# base.net
KiCad netlist of a schematic drawn in EAGLE
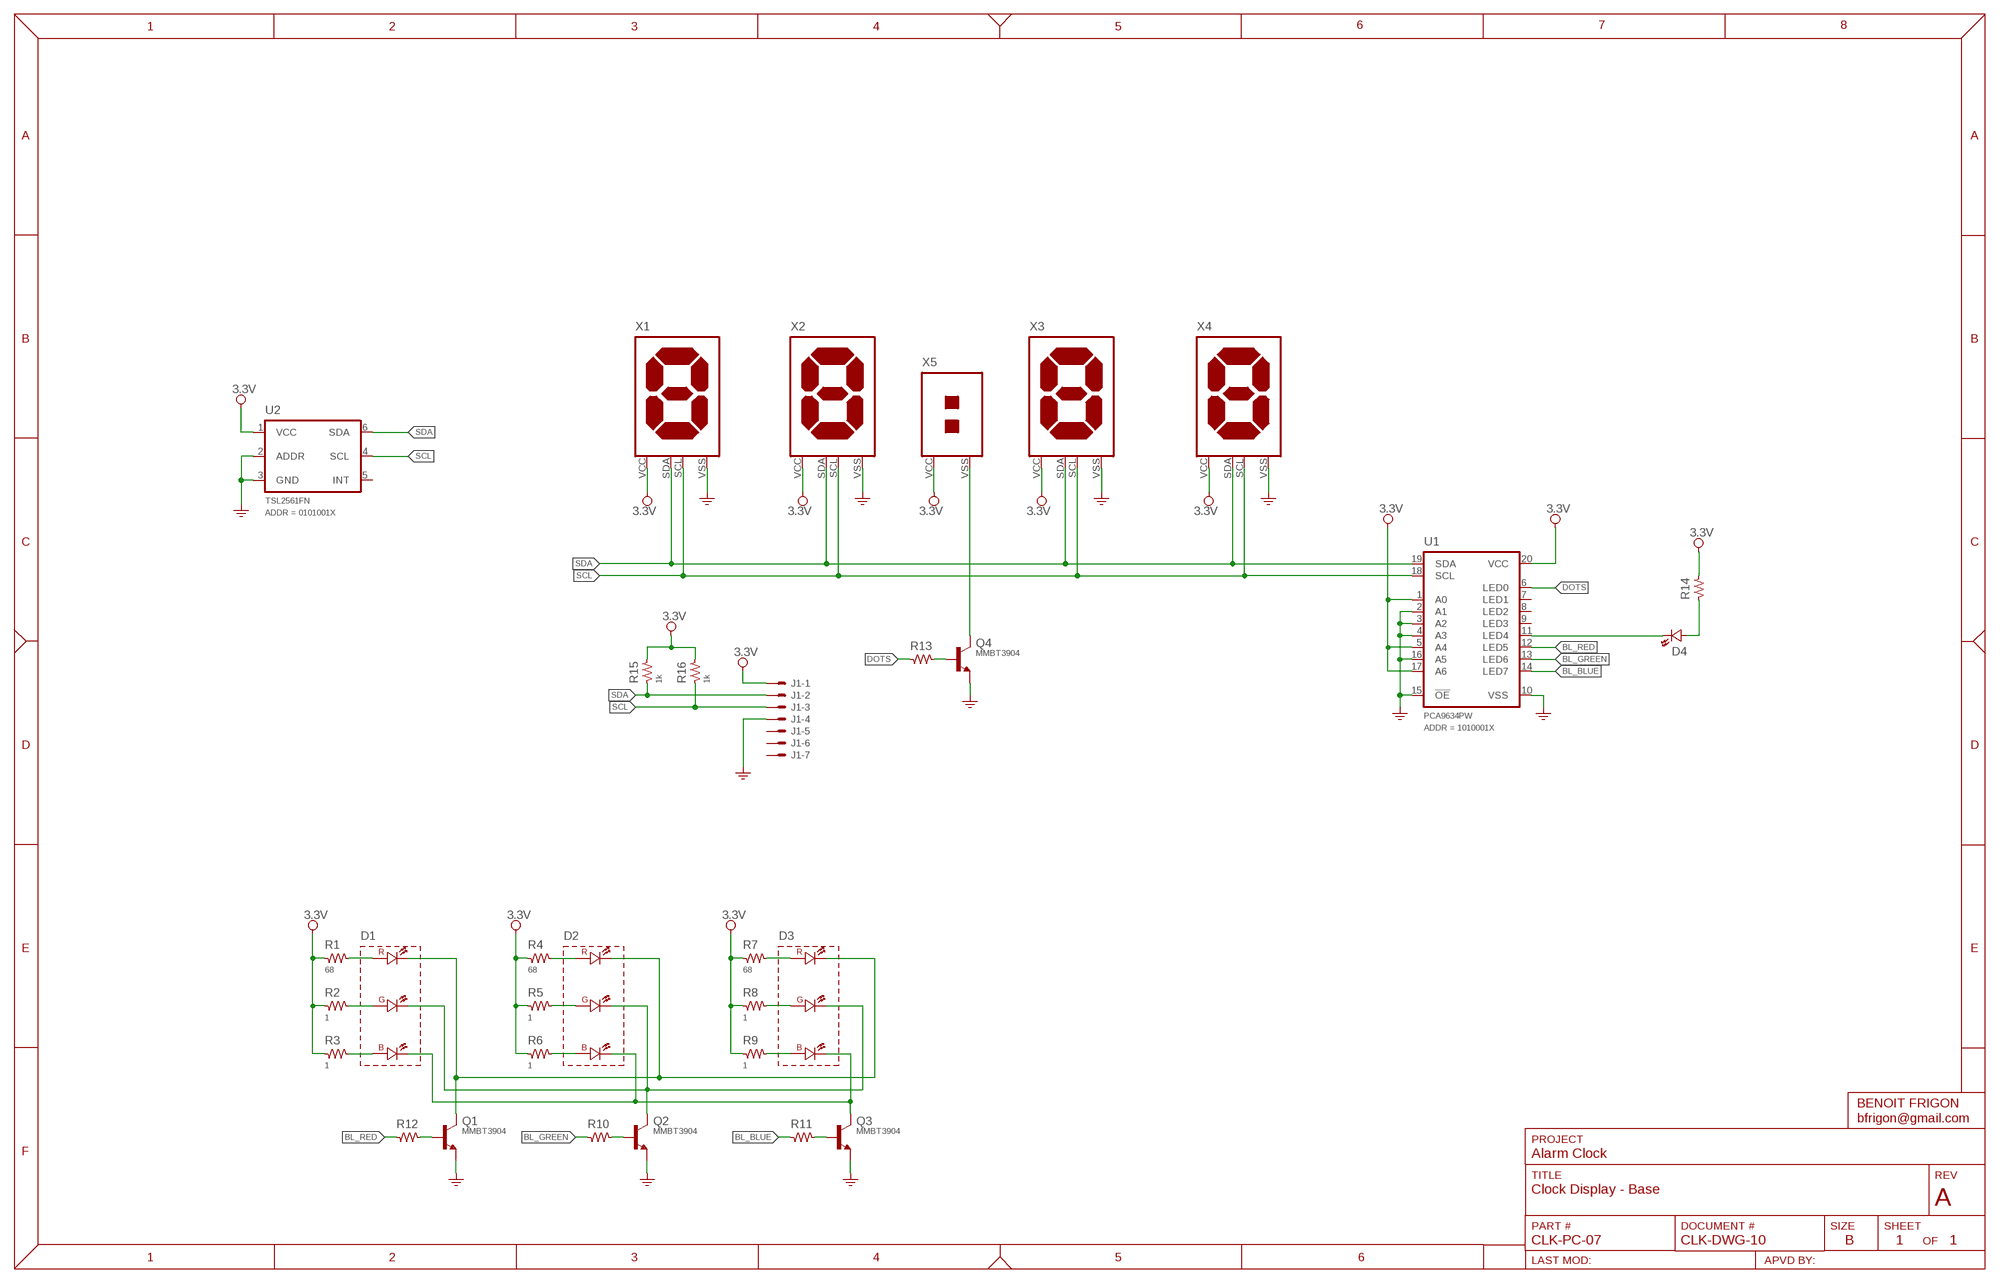
[diagram p0: schematic, sheet 1]

(export (version "E")
  (design (tool "Eeschema 10.0.6"))
  (components
    (comp (ref "D1")
      (value "SMP6-RGB")
      (footprint "eagle-import:LED_RGB_PLCC6")
      (fields (field (name "MFG") "Bivar") (field (name "MFG_1") "BIVAR") (field (name "SKU") "SMP6-RGB"))
      (libsource (lib "eagle-import") (part "SMP6-RGB"))
    )
    (comp (ref "D2")
      (value "SMP6-RGB")
      (footprint "eagle-import:LED_RGB_PLCC6")
      (fields (field (name "MFG") "Bivar"))
      (libsource (lib "eagle-import") (part "SMP6-RGB"))
    )
    (comp (ref "D3")
      (value "SMP6-RGB")
      (footprint "eagle-import:LED_RGB_PLCC6")
      (fields (field (name "MFG") "Bivar"))
      (libsource (lib "eagle-import") (part "SMP6-RGB"))
    )
    (comp (ref "D4")
      (value "{ATTR:COLOR}")
      (footprint "eagle-import:LED_3MM")
      (libsource (lib "eagle-import") (part "LED-T1"))
    )
    (comp (ref "J1")
      (value "SNG-2MM-HEADER-07-V")
      (footprint "eagle-import:DF3X-7P-2DSA")
      (fields
        (field (name "MFG") "Hirose Electronic")
        (field (name "PART_NO") "DF3A-7P-2DSA")
        (field (name "PRICE") "0.37")
        (field (name "SKU") "H2099-ND")
        (field (name "SUPPLIER") "Digi-Key")
      )
      (libsource (lib "eagle-import") (part "SNG-2MM-HEADER-07-V"))
    )
    (comp (ref "Q1")
      (value "MMBT3904")
      (footprint "eagle-import:SOT23")
      (libsource (lib "eagle-import") (part "MMBT3904"))
    )
    (comp (ref "Q2")
      (value "MMBT3904")
      (footprint "eagle-import:SOT23")
      (libsource (lib "eagle-import") (part "MMBT3904"))
    )
    (comp (ref "Q3")
      (value "MMBT3904")
      (footprint "eagle-import:SOT23")
      (libsource (lib "eagle-import") (part "MMBT3904"))
    )
    (comp (ref "Q4")
      (value "MMBT3904")
      (footprint "eagle-import:SOT23")
      (libsource (lib "eagle-import") (part "MMBT3904"))
    )
    (comp (ref "R1")
      (value "68")
      (footprint "eagle-import:SMD_0603")
      (libsource (lib "eagle-import") (part "RES-0603"))
    )
    (comp (ref "R2")
      (value "1")
      (footprint "eagle-import:SMD_0603")
      (description "{DESCRIPTION} - SMT 0603 - {VALUE}")
      (fields (field (name "PACKAGE") "SMT 0603"))
      (libsource (lib "eagle-import") (part "RES-0603"))
    )
    (comp (ref "R3")
      (value "1")
      (footprint "eagle-import:SMD_0603")
      (description "{DESCRIPTION} - SMT 0603 - {VALUE}")
      (fields (field (name "PACKAGE") "SMT 0603"))
      (libsource (lib "eagle-import") (part "RES-0603"))
    )
    (comp (ref "R4")
      (value "68")
      (footprint "eagle-import:SMD_0603")
      (libsource (lib "eagle-import") (part "RES-0603"))
    )
    (comp (ref "R5")
      (value "1")
      (footprint "eagle-import:SMD_0603")
      (description "{DESCRIPTION} - SMT 0603 - {VALUE}")
      (fields (field (name "PACKAGE") "SMT 0603"))
      (libsource (lib "eagle-import") (part "RES-0603"))
    )
    (comp (ref "R6")
      (value "1")
      (footprint "eagle-import:SMD_0603")
      (description "{DESCRIPTION} - SMT 0603 - {VALUE}")
      (fields (field (name "PACKAGE") "SMT 0603"))
      (libsource (lib "eagle-import") (part "RES-0603"))
    )
    (comp (ref "R7")
      (value "68")
      (footprint "eagle-import:SMD_0603")
      (libsource (lib "eagle-import") (part "RES-0603"))
    )
    (comp (ref "R8")
      (value "1")
      (footprint "eagle-import:SMD_0603")
      (description "{DESCRIPTION} - SMT 0603 - {VALUE}")
      (fields (field (name "PACKAGE") "SMT 0603"))
      (libsource (lib "eagle-import") (part "RES-0603"))
    )
    (comp (ref "R9")
      (value "1")
      (footprint "eagle-import:SMD_0603")
      (description "{DESCRIPTION} - SMT 0603 - {VALUE}")
      (fields (field (name "PACKAGE") "SMT 0603"))
      (libsource (lib "eagle-import") (part "RES-0603"))
    )
    (comp (ref "R10")
      (value "RES-0603")
      (footprint "eagle-import:SMD_0603")
      (libsource (lib "eagle-import") (part "RES-0603"))
    )
    (comp (ref "R11")
      (value "RES-0603")
      (footprint "eagle-import:SMD_0603")
      (libsource (lib "eagle-import") (part "RES-0603"))
    )
    (comp (ref "R12")
      (value "RES-0603")
      (footprint "eagle-import:SMD_0603")
      (libsource (lib "eagle-import") (part "RES-0603"))
    )
    (comp (ref "R13")
      (value "RES-0603")
      (footprint "eagle-import:SMD_0603")
      (description "{DESCRIPTION} - SMT 0603 - {VALUE}")
      (fields (field (name "PACKAGE") "SMT 0603"))
      (libsource (lib "eagle-import") (part "RES-0603"))
    )
    (comp (ref "R14")
      (value "RES-0603")
      (footprint "eagle-import:SMD_0603")
      (libsource (lib "eagle-import") (part "RES-0603"))
    )
    (comp (ref "R15")
      (value "1k")
      (footprint "eagle-import:SMD_0603")
      (libsource (lib "eagle-import") (part "RES-0603"))
    )
    (comp (ref "R16")
      (value "1k")
      (footprint "eagle-import:SMD_0603")
      (libsource (lib "eagle-import") (part "RES-0603"))
    )
    (comp (ref "U1")
      (value "PCA9634PW")
      (footprint "eagle-import:TSSOP20")
      (fields (field (name "MFG") "NXP Semiconductors") (field (name "ADDR") "1010001X"))
      (libsource (lib "eagle-import") (part "PCA9634PW"))
    )
    (comp (ref "U2")
      (value "TSL2561FN")
      (footprint "eagle-import:DFN-6")
      (fields (field (name "ADDR") "0101001X"))
      (libsource (lib "eagle-import") (part "TSL2561FN"))
    )
    (comp (ref "X1")
      (value "CLOCK_LED_SEGMENT")
      (footprint "eagle-import:CLOCK_LED_SEGMENT")
      (libsource (lib "eagle-import") (part "CLOCK_LED_SEGMENT"))
    )
    (comp (ref "X2")
      (value "CLOCK_LED_SEGMENT")
      (footprint "eagle-import:CLOCK_LED_SEGMENT")
      (libsource (lib "eagle-import") (part "CLOCK_LED_SEGMENT"))
    )
    (comp (ref "X3")
      (value "CLOCK_LED_SEGMENT")
      (footprint "eagle-import:CLOCK_LED_SEGMENT")
      (libsource (lib "eagle-import") (part "CLOCK_LED_SEGMENT"))
    )
    (comp (ref "X4")
      (value "CLOCK_LED_SEGMENT")
      (footprint "eagle-import:CLOCK_LED_SEGMENT")
      (libsource (lib "eagle-import") (part "CLOCK_LED_SEGMENT"))
    )
    (comp (ref "X5")
      (value "CLOCK_LED_DOTS")
      (footprint "eagle-import:CLOCK_LED_DOTS")
      (libsource (lib "eagle-import") (part "CLOCK_LED_DOTS"))
    )
  )
  (nets
    (net (code "1") (name "3.3V") (class "Default")
      (node (ref "J1") (pin "1") (pinfunction "S_1") (pintype "bidirectional"))
      (node (ref "R1") (pin "1") (pinfunction "1_1") (pintype "passive"))
      (node (ref "R14") (pin "2") (pinfunction "2_2") (pintype "passive"))
      (node (ref "R15") (pin "2") (pinfunction "2_2") (pintype "passive"))
      (node (ref "R16") (pin "2") (pinfunction "2_2") (pintype "passive"))
      (node (ref "R2") (pin "1") (pinfunction "1_1") (pintype "passive"))
      (node (ref "R3") (pin "1") (pinfunction "1_1") (pintype "passive"))
      (node (ref "R4") (pin "1") (pinfunction "1_1") (pintype "passive"))
      (node (ref "R5") (pin "1") (pinfunction "1_1") (pintype "passive"))
      (node (ref "R6") (pin "1") (pinfunction "1_1") (pintype "passive"))
      (node (ref "R7") (pin "1") (pinfunction "1_1") (pintype "passive"))
      (node (ref "R8") (pin "1") (pinfunction "1_1") (pintype "passive"))
      (node (ref "R9") (pin "1") (pinfunction "1_1") (pintype "passive"))
      (node (ref "U1") (pin "1") (pinfunction "A0_1") (pintype "bidirectional"))
      (node (ref "U1") (pin "17") (pinfunction "A6_17") (pintype "bidirectional"))
      (node (ref "U1") (pin "20") (pinfunction "VCC_20") (pintype "bidirectional"))
      (node (ref "U1") (pin "5") (pinfunction "A4_5") (pintype "bidirectional"))
      (node (ref "U2") (pin "1") (pinfunction "VCC_1") (pintype "bidirectional"))
      (node (ref "X1") (pin "VCC") (pinfunction "VCC_VCC") (pintype "bidirectional"))
      (node (ref "X2") (pin "VCC") (pinfunction "VCC_VCC") (pintype "bidirectional"))
      (node (ref "X3") (pin "VCC") (pinfunction "VCC_VCC") (pintype "bidirectional"))
      (node (ref "X4") (pin "VCC") (pinfunction "VCC_VCC") (pintype "bidirectional"))
      (node (ref "X5") (pin "VCC") (pinfunction "VCC_VCC") (pintype "bidirectional"))
    )
    (net (code "2") (name "BL_BLUE") (class "Default")
      (node (ref "R11") (pin "1") (pinfunction "1_1") (pintype "passive"))
      (node (ref "U1") (pin "14") (pinfunction "LED7_14") (pintype "bidirectional"))
    )
    (net (code "3") (name "BL_GREEN") (class "Default")
      (node (ref "R10") (pin "1") (pinfunction "1_1") (pintype "passive"))
      (node (ref "U1") (pin "13") (pinfunction "LED6_13") (pintype "bidirectional"))
    )
    (net (code "4") (name "BL_RED") (class "Default")
      (node (ref "R12") (pin "1") (pinfunction "1_1") (pintype "passive"))
      (node (ref "U1") (pin "12") (pinfunction "LED5_12") (pintype "bidirectional"))
    )
    (net (code "5") (name "DOTS") (class "Default")
      (node (ref "R13") (pin "1") (pinfunction "1_1") (pintype "passive"))
      (node (ref "U1") (pin "6") (pinfunction "LED0_6") (pintype "bidirectional"))
    )
    (net (code "6") (name "GND") (class "Default")
      (node (ref "J1") (pin "4") (pinfunction "S_4") (pintype "bidirectional"))
      (node (ref "Q1") (pin "2") (pinfunction "E_2") (pintype "passive"))
      (node (ref "Q2") (pin "2") (pinfunction "E_2") (pintype "passive"))
      (node (ref "Q3") (pin "2") (pinfunction "E_2") (pintype "passive"))
      (node (ref "Q4") (pin "2") (pinfunction "E_2") (pintype "passive"))
      (node (ref "U1") (pin "10") (pinfunction "VSS_10") (pintype "bidirectional"))
      (node (ref "U1") (pin "15") (pinfunction "~{OE}_15") (pintype "bidirectional"))
      (node (ref "U1") (pin "16") (pinfunction "A5_16") (pintype "bidirectional"))
      (node (ref "U1") (pin "2") (pinfunction "A1_2") (pintype "bidirectional"))
      (node (ref "U1") (pin "3") (pinfunction "A2_3") (pintype "bidirectional"))
      (node (ref "U1") (pin "4") (pinfunction "A3_4") (pintype "bidirectional"))
      (node (ref "U2") (pin "2") (pinfunction "ADDR_2") (pintype "bidirectional"))
      (node (ref "U2") (pin "3") (pinfunction "GND_3") (pintype "bidirectional"))
      (node (ref "X1") (pin "VSS") (pinfunction "VSS_VSS") (pintype "bidirectional"))
      (node (ref "X2") (pin "VSS") (pinfunction "VSS_VSS") (pintype "bidirectional"))
      (node (ref "X3") (pin "VSS") (pinfunction "VSS_VSS") (pintype "bidirectional"))
      (node (ref "X4") (pin "VSS") (pinfunction "VSS_VSS") (pintype "bidirectional"))
    )
    (net (code "7") (name "Net-(D1-BA)") (class "Default")
      (node (ref "D1") (pin "6") (pinfunction "BA_6") (pintype "passive"))
      (node (ref "R3") (pin "2") (pinfunction "2_2") (pintype "passive"))
    )
    (net (code "8") (name "Net-(D1-BK)") (class "Default")
      (node (ref "D1") (pin "5") (pinfunction "BK_5") (pintype "passive"))
      (node (ref "D2") (pin "5") (pinfunction "BK_5") (pintype "passive"))
      (node (ref "D3") (pin "5") (pinfunction "BK_5") (pintype "passive"))
      (node (ref "Q3") (pin "3") (pinfunction "C_3") (pintype "passive"))
    )
    (net (code "9") (name "Net-(D1-GA)") (class "Default")
      (node (ref "D1") (pin "2") (pinfunction "GA_2") (pintype "passive"))
      (node (ref "R2") (pin "2") (pinfunction "2_2") (pintype "passive"))
    )
    (net (code "10") (name "Net-(D1-GK)") (class "Default")
      (node (ref "D1") (pin "1") (pinfunction "GK_1") (pintype "passive"))
      (node (ref "D2") (pin "1") (pinfunction "GK_1") (pintype "passive"))
      (node (ref "D3") (pin "1") (pinfunction "GK_1") (pintype "passive"))
      (node (ref "Q2") (pin "3") (pinfunction "C_3") (pintype "passive"))
    )
    (net (code "11") (name "Net-(D1-RA)") (class "Default")
      (node (ref "D1") (pin "4") (pinfunction "RA_4") (pintype "passive"))
      (node (ref "R1") (pin "2") (pinfunction "2_2") (pintype "passive"))
    )
    (net (code "12") (name "Net-(D1-RK)") (class "Default")
      (node (ref "D1") (pin "3") (pinfunction "RK_3") (pintype "passive"))
      (node (ref "D2") (pin "3") (pinfunction "RK_3") (pintype "passive"))
      (node (ref "D3") (pin "3") (pinfunction "RK_3") (pintype "passive"))
      (node (ref "Q1") (pin "3") (pinfunction "C_3") (pintype "passive"))
    )
    (net (code "13") (name "Net-(D2-BA)") (class "Default")
      (node (ref "D2") (pin "6") (pinfunction "BA_6") (pintype "passive"))
      (node (ref "R6") (pin "2") (pinfunction "2_2") (pintype "passive"))
    )
    (net (code "14") (name "Net-(D2-GA)") (class "Default")
      (node (ref "D2") (pin "2") (pinfunction "GA_2") (pintype "passive"))
      (node (ref "R5") (pin "2") (pinfunction "2_2") (pintype "passive"))
    )
    (net (code "15") (name "Net-(D2-RA)") (class "Default")
      (node (ref "D2") (pin "4") (pinfunction "RA_4") (pintype "passive"))
      (node (ref "R4") (pin "2") (pinfunction "2_2") (pintype "passive"))
    )
    (net (code "16") (name "Net-(D3-BA)") (class "Default")
      (node (ref "D3") (pin "6") (pinfunction "BA_6") (pintype "passive"))
      (node (ref "R9") (pin "2") (pinfunction "2_2") (pintype "passive"))
    )
    (net (code "17") (name "Net-(D3-GA)") (class "Default")
      (node (ref "D3") (pin "2") (pinfunction "GA_2") (pintype "passive"))
      (node (ref "R8") (pin "2") (pinfunction "2_2") (pintype "passive"))
    )
    (net (code "18") (name "Net-(D3-RA)") (class "Default")
      (node (ref "D3") (pin "4") (pinfunction "RA_4") (pintype "passive"))
      (node (ref "R7") (pin "2") (pinfunction "2_2") (pintype "passive"))
    )
    (net (code "19") (name "Net-(D4-PadA)") (class "Default")
      (node (ref "D4") (pin "A") (pinfunction "A_A") (pintype "passive"))
      (node (ref "R14") (pin "1") (pinfunction "1_1") (pintype "passive"))
    )
    (net (code "20") (name "Net-(Q1-B)") (class "Default")
      (node (ref "Q1") (pin "1") (pinfunction "B_1") (pintype "passive"))
      (node (ref "R12") (pin "2") (pinfunction "2_2") (pintype "passive"))
    )
    (net (code "21") (name "Net-(Q2-B)") (class "Default")
      (node (ref "Q2") (pin "1") (pinfunction "B_1") (pintype "passive"))
      (node (ref "R10") (pin "2") (pinfunction "2_2") (pintype "passive"))
    )
    (net (code "22") (name "Net-(Q3-B)") (class "Default")
      (node (ref "Q3") (pin "1") (pinfunction "B_1") (pintype "passive"))
      (node (ref "R11") (pin "2") (pinfunction "2_2") (pintype "passive"))
    )
    (net (code "23") (name "Net-(Q4-B)") (class "Default")
      (node (ref "Q4") (pin "1") (pinfunction "B_1") (pintype "passive"))
      (node (ref "R13") (pin "2") (pinfunction "2_2") (pintype "passive"))
    )
    (net (code "24") (name "Net-(Q4-C)") (class "Default")
      (node (ref "Q4") (pin "3") (pinfunction "C_3") (pintype "passive"))
      (node (ref "X5") (pin "VSS") (pinfunction "VSS_VSS") (pintype "bidirectional"))
    )
    (net (code "25") (name "Net-(U1-LED4)") (class "Default")
      (node (ref "D4") (pin "K") (pinfunction "K_K") (pintype "passive"))
      (node (ref "U1") (pin "11") (pinfunction "LED4_11") (pintype "bidirectional"))
    )
    (net (code "26") (name "SCL") (class "Default")
      (node (ref "J1") (pin "3") (pinfunction "S_3") (pintype "bidirectional"))
      (node (ref "R16") (pin "1") (pinfunction "1_1") (pintype "passive"))
      (node (ref "U1") (pin "18") (pinfunction "SCL_18") (pintype "bidirectional"))
      (node (ref "U2") (pin "4") (pinfunction "SCL_4") (pintype "bidirectional"))
      (node (ref "X1") (pin "SCL") (pinfunction "SCL_SCL") (pintype "bidirectional"))
      (node (ref "X2") (pin "SCL") (pinfunction "SCL_SCL") (pintype "bidirectional"))
      (node (ref "X3") (pin "SCL") (pinfunction "SCL_SCL") (pintype "bidirectional"))
      (node (ref "X4") (pin "SCL") (pinfunction "SCL_SCL") (pintype "bidirectional"))
    )
    (net (code "27") (name "SDA") (class "Default")
      (node (ref "J1") (pin "2") (pinfunction "S_2") (pintype "bidirectional"))
      (node (ref "R15") (pin "1") (pinfunction "1_1") (pintype "passive"))
      (node (ref "U1") (pin "19") (pinfunction "SDA_19") (pintype "bidirectional"))
      (node (ref "U2") (pin "6") (pinfunction "SDA_6") (pintype "bidirectional"))
      (node (ref "X1") (pin "SDA") (pinfunction "SDA_SDA") (pintype "bidirectional"))
      (node (ref "X2") (pin "SDA") (pinfunction "SDA_SDA") (pintype "bidirectional"))
      (node (ref "X3") (pin "SDA") (pinfunction "SDA_SDA") (pintype "bidirectional"))
      (node (ref "X4") (pin "SDA") (pinfunction "SDA_SDA") (pintype "bidirectional"))
    )
    (net (code "28") (name "unconnected-(J1E-S-Pad5)") (class "Default")
      (node (ref "J1") (pin "5") (pinfunction "S_5") (pintype "bidirectional"))
    )
    (net (code "29") (name "unconnected-(J1F-S-Pad6)") (class "Default")
      (node (ref "J1") (pin "6") (pinfunction "S_6") (pintype "bidirectional"))
    )
    (net (code "30") (name "unconnected-(J1G-S-Pad7)") (class "Default")
      (node (ref "J1") (pin "7") (pinfunction "S_7") (pintype "bidirectional"))
    )
    (net (code "31") (name "unconnected-(U1-LED1-Pad7)") (class "Default")
      (node (ref "U1") (pin "7") (pinfunction "LED1_7") (pintype "bidirectional"))
    )
    (net (code "32") (name "unconnected-(U1-LED2-Pad8)") (class "Default")
      (node (ref "U1") (pin "8") (pinfunction "LED2_8") (pintype "bidirectional"))
    )
    (net (code "33") (name "unconnected-(U1-LED3-Pad9)") (class "Default")
      (node (ref "U1") (pin "9") (pinfunction "LED3_9") (pintype "bidirectional"))
    )
    (net (code "34") (name "unconnected-(U2-INT-Pad5)") (class "Default")
      (node (ref "U2") (pin "5") (pinfunction "INT_5") (pintype "bidirectional"))
    )
  )
)
